# M228.net
KiCad netlist of a schematic drawn in EAGLE
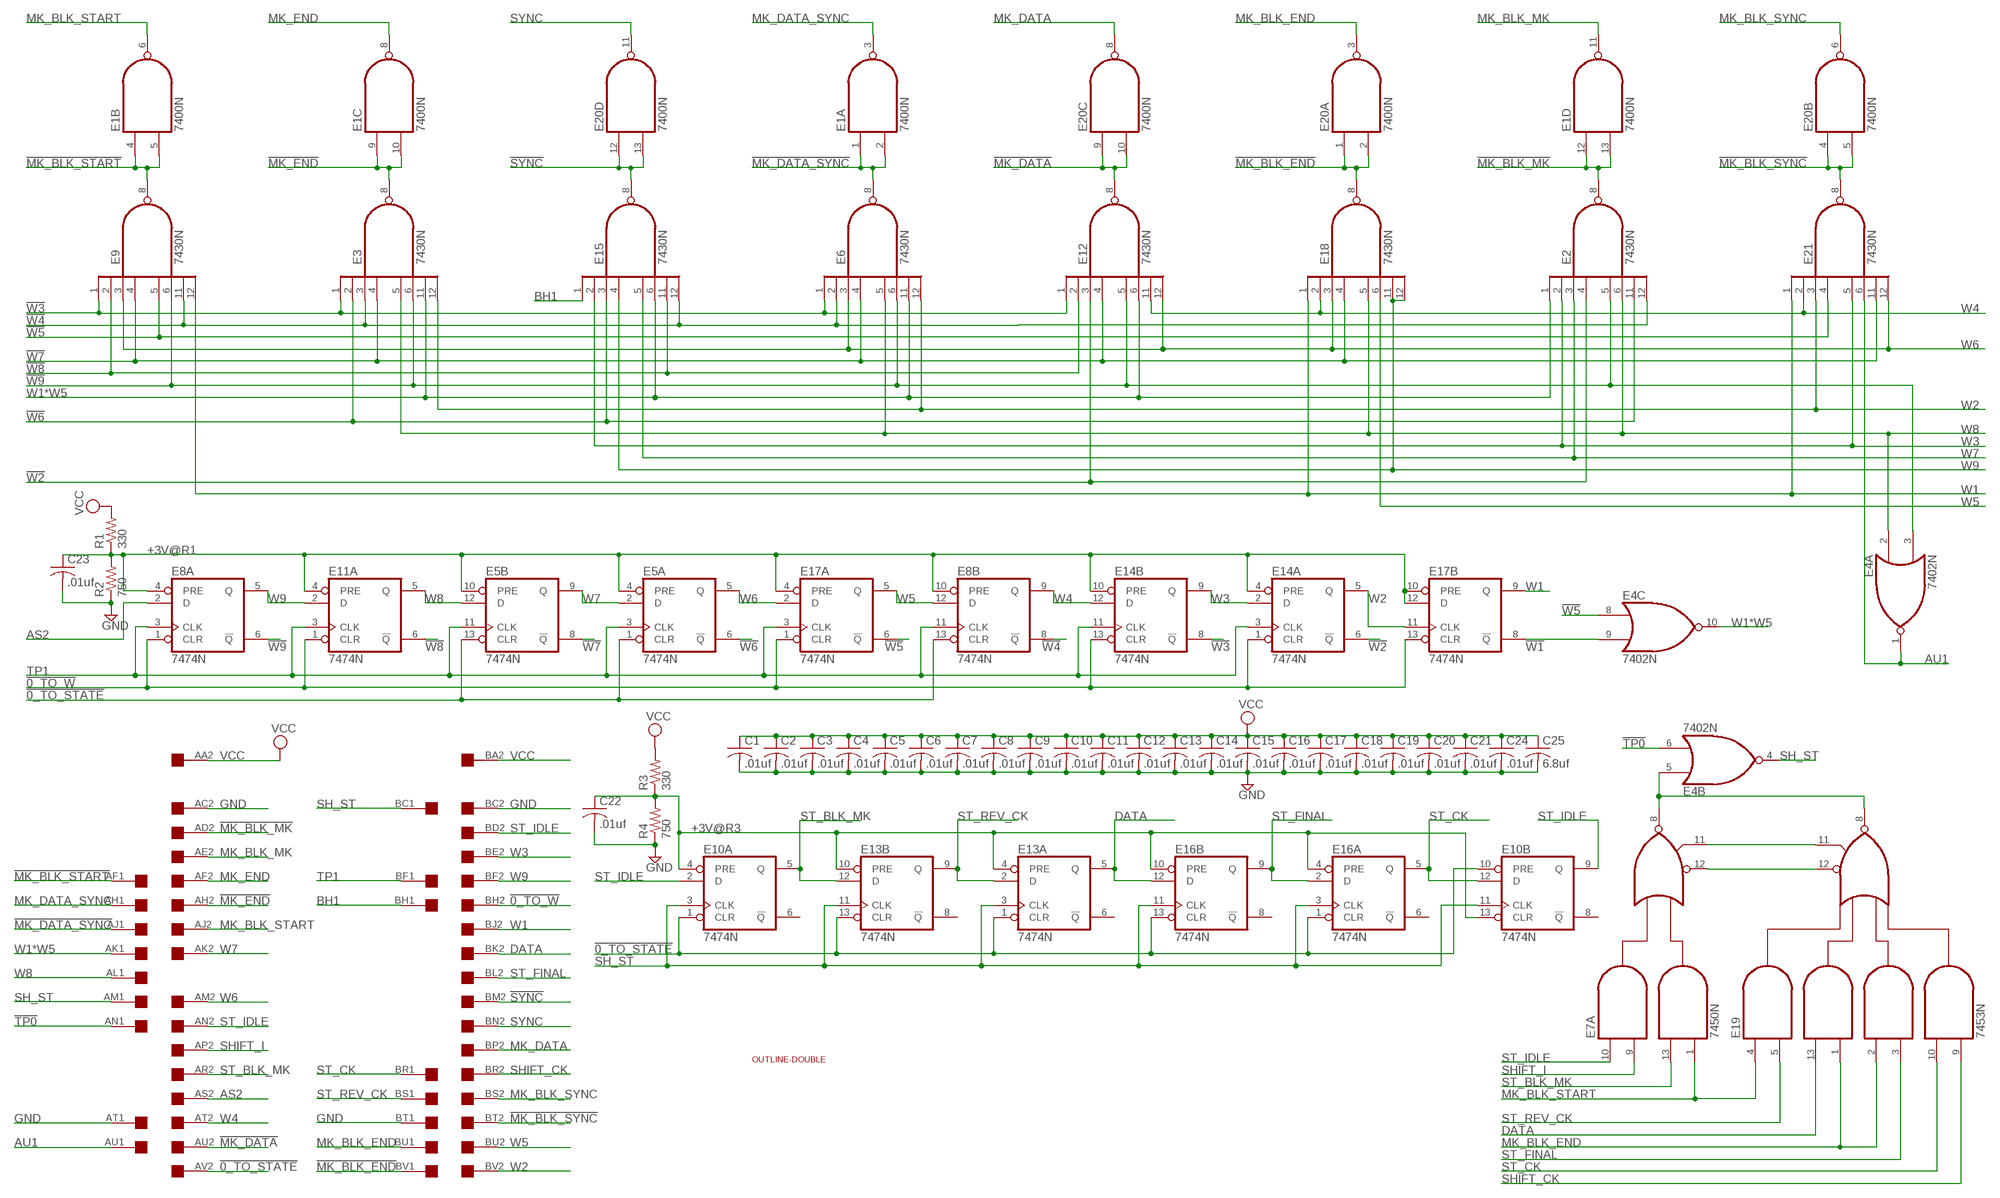
[diagram p0: schematic, sheet 1]

(export (version "E")
  (design (tool "Eeschema 10.0.6"))
  (components
    (comp (ref "C1")
      (value ".01uf")
      (footprint "eagle-import:C050-025X075")
      (libsource (lib "eagle-import") (part "C-US050-025X075"))
    )
    (comp (ref "C2")
      (value ".01uf")
      (footprint "eagle-import:C050-025X075")
      (libsource (lib "eagle-import") (part "C-US050-025X075"))
    )
    (comp (ref "C3")
      (value ".01uf")
      (footprint "eagle-import:C050-025X075")
      (libsource (lib "eagle-import") (part "C-US050-025X075"))
    )
    (comp (ref "C4")
      (value ".01uf")
      (footprint "eagle-import:C050-025X075")
      (libsource (lib "eagle-import") (part "C-US050-025X075"))
    )
    (comp (ref "C5")
      (value ".01uf")
      (footprint "eagle-import:C050-025X075")
      (libsource (lib "eagle-import") (part "C-US050-025X075"))
    )
    (comp (ref "C6")
      (value ".01uf")
      (footprint "eagle-import:C050-025X075")
      (libsource (lib "eagle-import") (part "C-US050-025X075"))
    )
    (comp (ref "C7")
      (value ".01uf")
      (footprint "eagle-import:C050-025X075")
      (libsource (lib "eagle-import") (part "C-US050-025X075"))
    )
    (comp (ref "C8")
      (value ".01uf")
      (footprint "eagle-import:C050-025X075")
      (libsource (lib "eagle-import") (part "C-US050-025X075"))
    )
    (comp (ref "C9")
      (value ".01uf")
      (footprint "eagle-import:C050-025X075")
      (libsource (lib "eagle-import") (part "C-US050-025X075"))
    )
    (comp (ref "C10")
      (value ".01uf")
      (footprint "eagle-import:C050-025X075")
      (libsource (lib "eagle-import") (part "C-US050-025X075"))
    )
    (comp (ref "C11")
      (value ".01uf")
      (footprint "eagle-import:C050-025X075")
      (libsource (lib "eagle-import") (part "C-US050-025X075"))
    )
    (comp (ref "C12")
      (value ".01uf")
      (footprint "eagle-import:C050-025X075")
      (libsource (lib "eagle-import") (part "C-US050-025X075"))
    )
    (comp (ref "C13")
      (value ".01uf")
      (footprint "eagle-import:C050-025X075")
      (libsource (lib "eagle-import") (part "C-US050-025X075"))
    )
    (comp (ref "C14")
      (value ".01uf")
      (footprint "eagle-import:C050-025X075")
      (libsource (lib "eagle-import") (part "C-US050-025X075"))
    )
    (comp (ref "C15")
      (value ".01uf")
      (footprint "eagle-import:C050-025X075")
      (libsource (lib "eagle-import") (part "C-US050-025X075"))
    )
    (comp (ref "C16")
      (value ".01uf")
      (footprint "eagle-import:C050-025X075")
      (libsource (lib "eagle-import") (part "C-US050-025X075"))
    )
    (comp (ref "C17")
      (value ".01uf")
      (footprint "eagle-import:C050-025X075")
      (libsource (lib "eagle-import") (part "C-US050-025X075"))
    )
    (comp (ref "C18")
      (value ".01uf")
      (footprint "eagle-import:C050-025X075")
      (libsource (lib "eagle-import") (part "C-US050-025X075"))
    )
    (comp (ref "C19")
      (value ".01uf")
      (footprint "eagle-import:C050-025X075")
      (libsource (lib "eagle-import") (part "C-US050-025X075"))
    )
    (comp (ref "C20")
      (value ".01uf")
      (footprint "eagle-import:C050-025X075")
      (libsource (lib "eagle-import") (part "C-US050-025X075"))
    )
    (comp (ref "C21")
      (value ".01uf")
      (footprint "eagle-import:C050-025X075")
      (libsource (lib "eagle-import") (part "C-US050-025X075"))
    )
    (comp (ref "C22")
      (value ".01uf")
      (footprint "eagle-import:C050-025X075")
      (libsource (lib "eagle-import") (part "C-US050-025X075"))
    )
    (comp (ref "C23")
      (value ".01uf")
      (footprint "eagle-import:C050-025X075")
      (libsource (lib "eagle-import") (part "C-US050-025X075"))
    )
    (comp (ref "C24")
      (value ".01uf")
      (footprint "eagle-import:C050-025X075")
      (libsource (lib "eagle-import") (part "C-US050-025X075"))
    )
    (comp (ref "C25")
      (value "6.8uf")
      (footprint "eagle-import:C150-054X183")
      (libsource (lib "eagle-import") (part "C-US150-054X183"))
    )
    (comp (ref "E1")
      (value "7400N")
      (footprint "eagle-import:DIL14")
      (libsource (lib "eagle-import") (part "7400N"))
    )
    (comp (ref "E2")
      (value "7430N")
      (footprint "eagle-import:DIL14")
      (libsource (lib "eagle-import") (part "7430N"))
    )
    (comp (ref "E3")
      (value "7430N")
      (footprint "eagle-import:DIL14")
      (libsource (lib "eagle-import") (part "7430N"))
    )
    (comp (ref "E4")
      (value "7402N")
      (footprint "eagle-import:DIL14")
      (libsource (lib "eagle-import") (part "7402N"))
    )
    (comp (ref "E5")
      (value "7474N")
      (footprint "eagle-import:DIL14")
      (libsource (lib "eagle-import") (part "7474NS"))
    )
    (comp (ref "E6")
      (value "7430N")
      (footprint "eagle-import:DIL14")
      (libsource (lib "eagle-import") (part "7430N"))
    )
    (comp (ref "E7")
      (value "7450N")
      (footprint "eagle-import:DIL14")
      (libsource (lib "eagle-import") (part "7450N"))
    )
    (comp (ref "E8")
      (value "7474N")
      (footprint "eagle-import:DIL14")
      (libsource (lib "eagle-import") (part "7474NS"))
    )
    (comp (ref "E9")
      (value "7430N")
      (footprint "eagle-import:DIL14")
      (libsource (lib "eagle-import") (part "7430N"))
    )
    (comp (ref "E10")
      (value "7474N")
      (footprint "eagle-import:DIL14")
      (libsource (lib "eagle-import") (part "7474NS"))
    )
    (comp (ref "E11")
      (value "7474N")
      (footprint "eagle-import:DIL14")
      (libsource (lib "eagle-import") (part "7474NS"))
    )
    (comp (ref "E12")
      (value "7430N")
      (footprint "eagle-import:DIL14")
      (libsource (lib "eagle-import") (part "7430N"))
    )
    (comp (ref "E13")
      (value "7474N")
      (footprint "eagle-import:DIL14")
      (libsource (lib "eagle-import") (part "7474NS"))
    )
    (comp (ref "E14")
      (value "7474N")
      (footprint "eagle-import:DIL14")
      (libsource (lib "eagle-import") (part "7474NS"))
    )
    (comp (ref "E15")
      (value "7430N")
      (footprint "eagle-import:DIL14")
      (libsource (lib "eagle-import") (part "7430N"))
    )
    (comp (ref "E16")
      (value "7474N")
      (footprint "eagle-import:DIL14")
      (libsource (lib "eagle-import") (part "7474NS"))
    )
    (comp (ref "E17")
      (value "7474N")
      (footprint "eagle-import:DIL14")
      (libsource (lib "eagle-import") (part "7474NS"))
    )
    (comp (ref "E18")
      (value "7430N")
      (footprint "eagle-import:DIL14")
      (libsource (lib "eagle-import") (part "7430N"))
    )
    (comp (ref "E19")
      (value "7453N")
      (footprint "eagle-import:DIL14")
      (libsource (lib "eagle-import") (part "7453N"))
    )
    (comp (ref "E20")
      (value "7400N")
      (footprint "eagle-import:DIL14")
      (libsource (lib "eagle-import") (part "7400N"))
    )
    (comp (ref "E21")
      (value "7430N")
      (footprint "eagle-import:DIL14")
      (libsource (lib "eagle-import") (part "7430N"))
    )
    (comp (ref "R1")
      (value "330")
      (footprint "eagle-import:0207_10")
      (libsource (lib "eagle-import") (part "R-US_0207/10"))
    )
    (comp (ref "R2")
      (value "750")
      (footprint "eagle-import:0207_10")
      (libsource (lib "eagle-import") (part "R-US_0207/10"))
    )
    (comp (ref "R3")
      (value "330")
      (footprint "eagle-import:0207_10")
      (libsource (lib "eagle-import") (part "R-US_0207/10"))
    )
    (comp (ref "R4")
      (value "750")
      (footprint "eagle-import:0207_10")
      (libsource (lib "eagle-import") (part "R-US_0207/10"))
    )
    (comp (ref "U$1")
      (value "OUTLINE-DOUBLE")
      (footprint "eagle-import:DOUBLE")
      (libsource (lib "eagle-import") (part "OUTLINE-DOUBLE"))
    )
    (comp (ref "U$5")
      (value "DOUBLE")
      (footprint "eagle-import:EDGE-CON4")
      (libsource (lib "eagle-import") (part "DOUBLE"))
    )
  )
  (nets
    (net (code "1") (name "/+3V@R1") (class "Default")
      (node (ref "C23") (pin "1") (pinfunction "1_1") (pintype "passive"))
      (node (ref "E11") (pin "4") (pinfunction "PRE_4") (pintype "input"))
      (node (ref "E14") (pin "10") (pinfunction "PRE_10") (pintype "input"))
      (node (ref "E14") (pin "4") (pinfunction "PRE_4") (pintype "input"))
      (node (ref "E17") (pin "10") (pinfunction "PRE_10") (pintype "input"))
      (node (ref "E17") (pin "12") (pinfunction "D_12") (pintype "input"))
      (node (ref "E17") (pin "4") (pinfunction "PRE_4") (pintype "input"))
      (node (ref "E5") (pin "10") (pinfunction "PRE_10") (pintype "input"))
      (node (ref "E5") (pin "4") (pinfunction "PRE_4") (pintype "input"))
      (node (ref "E8") (pin "10") (pinfunction "PRE_10") (pintype "input"))
      (node (ref "E8") (pin "4") (pinfunction "PRE_4") (pintype "input"))
      (node (ref "R1") (pin "1") (pinfunction "1_1") (pintype "passive"))
      (node (ref "R2") (pin "2") (pinfunction "2_2") (pintype "passive"))
    )
    (net (code "2") (name "/+3V@R3") (class "Default")
      (node (ref "C22") (pin "1") (pinfunction "1_1") (pintype "passive"))
      (node (ref "E10") (pin "13") (pinfunction "CLR_13") (pintype "input"))
      (node (ref "E10") (pin "4") (pinfunction "PRE_4") (pintype "input"))
      (node (ref "E13") (pin "10") (pinfunction "PRE_10") (pintype "input"))
      (node (ref "E13") (pin "4") (pinfunction "PRE_4") (pintype "input"))
      (node (ref "E16") (pin "10") (pinfunction "PRE_10") (pintype "input"))
      (node (ref "E16") (pin "4") (pinfunction "PRE_4") (pintype "input"))
      (node (ref "R3") (pin "1") (pinfunction "1_1") (pintype "passive"))
      (node (ref "R4") (pin "2") (pinfunction "2_2") (pintype "passive"))
    )
    (net (code "3") (name "/AS2") (class "Default")
      (node (ref "E8") (pin "2") (pinfunction "D_2") (pintype "input"))
      (node (ref "U$5") (pin "AS2") (pinfunction "1_AS2") (pintype "bidirectional"))
    )
    (net (code "4") (name "/AU1") (class "Default")
      (node (ref "E21") (pin "6") (pinfunction "I5_6") (pintype "input"))
      (node (ref "E4") (pin "1") (pinfunction "O_1") (pintype "output"))
      (node (ref "U$5") (pin "AU1") (pinfunction "1_AU1") (pintype "bidirectional"))
    )
    (net (code "5") (name "/BH1") (class "Default")
      (node (ref "E15") (pin "1") (pinfunction "I0_1") (pintype "input"))
      (node (ref "U$5") (pin "BH1") (pinfunction "1_BH1") (pintype "bidirectional"))
    )
    (net (code "6") (name "/DATA") (class "Default")
      (node (ref "E13") (pin "5") (pinfunction "Q_5") (pintype "output"))
      (node (ref "E16") (pin "12") (pinfunction "D_12") (pintype "input"))
      (node (ref "E19") (pin "13") (pinfunction "I3_13") (pintype "input"))
      (node (ref "U$5") (pin "BK2") (pinfunction "1_BK2") (pintype "bidirectional"))
    )
    (net (code "7") (name "/MK_BLK_END") (class "Default")
      (node (ref "E19") (pin "1") (pinfunction "I4_1") (pintype "input"))
      (node (ref "E19") (pin "2") (pinfunction "I5_2") (pintype "input"))
      (node (ref "E20") (pin "3") (pinfunction "O_3") (pintype "output"))
      (node (ref "U$5") (pin "BU1") (pinfunction "1_BU1") (pintype "bidirectional"))
    )
    (net (code "8") (name "/MK_BLK_MK") (class "Default")
      (node (ref "E1") (pin "11") (pinfunction "O_11") (pintype "output"))
      (node (ref "U$5") (pin "AE2") (pinfunction "1_AE2") (pintype "bidirectional"))
    )
    (net (code "9") (name "/MK_BLK_START") (class "Default")
      (node (ref "E1") (pin "6") (pinfunction "O_6") (pintype "output"))
      (node (ref "E19") (pin "4") (pinfunction "I1_4") (pintype "input"))
      (node (ref "E7") (pin "1") (pinfunction "I4_1") (pintype "input"))
      (node (ref "U$5") (pin "AJ2") (pinfunction "1_AJ2") (pintype "bidirectional"))
    )
    (net (code "10") (name "/MK_BLK_SYNC") (class "Default")
      (node (ref "E20") (pin "6") (pinfunction "O_6") (pintype "output"))
      (node (ref "U$5") (pin "BS2") (pinfunction "1_BS2") (pintype "bidirectional"))
    )
    (net (code "11") (name "/MK_DATA") (class "Default")
      (node (ref "E20") (pin "8") (pinfunction "O_8") (pintype "output"))
      (node (ref "U$5") (pin "BP2") (pinfunction "1_BP2") (pintype "bidirectional"))
    )
    (net (code "12") (name "/MK_DATA_SYNC") (class "Default")
      (node (ref "E1") (pin "3") (pinfunction "O_3") (pintype "output"))
      (node (ref "U$5") (pin "AH1") (pinfunction "1_AH1") (pintype "bidirectional"))
    )
    (net (code "13") (name "/MK_END") (class "Default")
      (node (ref "E1") (pin "8") (pinfunction "O_8") (pintype "output"))
      (node (ref "U$5") (pin "AF2") (pinfunction "1_AF2") (pintype "bidirectional"))
    )
    (net (code "14") (name "/SHIFT_CK") (class "Default")
      (node (ref "E19") (pin "9") (pinfunction "I8_9") (pintype "input"))
      (node (ref "U$5") (pin "BR2") (pinfunction "1_BR2") (pintype "bidirectional"))
    )
    (net (code "15") (name "/SHIFT_I") (class "Default")
      (node (ref "E7") (pin "9") (pinfunction "I2_9") (pintype "input"))
      (node (ref "U$5") (pin "AP2") (pinfunction "1_AP2") (pintype "bidirectional"))
    )
    (net (code "16") (name "/SH_ST") (class "Default")
      (node (ref "E10") (pin "11") (pinfunction "CLK_11") (pintype "input"))
      (node (ref "E10") (pin "3") (pinfunction "CLK_3") (pintype "input"))
      (node (ref "E13") (pin "11") (pinfunction "CLK_11") (pintype "input"))
      (node (ref "E13") (pin "3") (pinfunction "CLK_3") (pintype "input"))
      (node (ref "E16") (pin "11") (pinfunction "CLK_11") (pintype "input"))
      (node (ref "E16") (pin "3") (pinfunction "CLK_3") (pintype "input"))
      (node (ref "E4") (pin "4") (pinfunction "O_4") (pintype "output"))
      (node (ref "U$5") (pin "AM1") (pinfunction "1_AM1") (pintype "bidirectional"))
      (node (ref "U$5") (pin "BC1") (pinfunction "1_BC1") (pintype "bidirectional"))
    )
    (net (code "17") (name "/ST_BLK_MK") (class "Default")
      (node (ref "E10") (pin "5") (pinfunction "Q_5") (pintype "output"))
      (node (ref "E13") (pin "12") (pinfunction "D_12") (pintype "input"))
      (node (ref "E7") (pin "13") (pinfunction "I3_13") (pintype "input"))
      (node (ref "U$5") (pin "AR2") (pinfunction "1_AR2") (pintype "bidirectional"))
    )
    (net (code "18") (name "/ST_CK") (class "Default")
      (node (ref "E10") (pin "12") (pinfunction "D_12") (pintype "input"))
      (node (ref "E16") (pin "5") (pinfunction "Q_5") (pintype "output"))
      (node (ref "E19") (pin "10") (pinfunction "I7_10") (pintype "input"))
      (node (ref "U$5") (pin "BR1") (pinfunction "1_BR1") (pintype "bidirectional"))
    )
    (net (code "19") (name "/ST_FINAL") (class "Default")
      (node (ref "E16") (pin "2") (pinfunction "D_2") (pintype "input"))
      (node (ref "E16") (pin "9") (pinfunction "Q_9") (pintype "output"))
      (node (ref "E19") (pin "3") (pinfunction "I6_3") (pintype "input"))
      (node (ref "U$5") (pin "BL2") (pinfunction "1_BL2") (pintype "bidirectional"))
    )
    (net (code "20") (name "/ST_IDLE") (class "Default")
      (node (ref "E10") (pin "2") (pinfunction "D_2") (pintype "input"))
      (node (ref "E10") (pin "9") (pinfunction "Q_9") (pintype "output"))
      (node (ref "E7") (pin "10") (pinfunction "I1_10") (pintype "input"))
      (node (ref "U$5") (pin "AN2") (pinfunction "1_AN2") (pintype "bidirectional"))
      (node (ref "U$5") (pin "BD2") (pinfunction "1_BD2") (pintype "bidirectional"))
    )
    (net (code "21") (name "/ST_REV_CK") (class "Default")
      (node (ref "E13") (pin "2") (pinfunction "D_2") (pintype "input"))
      (node (ref "E13") (pin "9") (pinfunction "Q_9") (pintype "output"))
      (node (ref "E19") (pin "5") (pinfunction "I2_5") (pintype "input"))
      (node (ref "U$5") (pin "BS1") (pinfunction "1_BS1") (pintype "bidirectional"))
    )
    (net (code "22") (name "/SYNC") (class "Default")
      (node (ref "E20") (pin "11") (pinfunction "O_11") (pintype "output"))
      (node (ref "U$5") (pin "BN2") (pinfunction "1_BN2") (pintype "bidirectional"))
    )
    (net (code "23") (name "/TP1") (class "Default")
      (node (ref "E11") (pin "3") (pinfunction "CLK_3") (pintype "input"))
      (node (ref "E14") (pin "11") (pinfunction "CLK_11") (pintype "input"))
      (node (ref "E14") (pin "3") (pinfunction "CLK_3") (pintype "input"))
      (node (ref "E17") (pin "3") (pinfunction "CLK_3") (pintype "input"))
      (node (ref "E5") (pin "11") (pinfunction "CLK_11") (pintype "input"))
      (node (ref "E5") (pin "3") (pinfunction "CLK_3") (pintype "input"))
      (node (ref "E8") (pin "11") (pinfunction "CLK_11") (pintype "input"))
      (node (ref "E8") (pin "3") (pinfunction "CLK_3") (pintype "input"))
      (node (ref "U$5") (pin "BF1") (pinfunction "1_BF1") (pintype "bidirectional"))
    )
    (net (code "24") (name "/W1") (class "Default")
      (node (ref "E17") (pin "9") (pinfunction "Q_9") (pintype "output"))
      (node (ref "E18") (pin "1") (pinfunction "I0_1") (pintype "input"))
      (node (ref "E21") (pin "1") (pinfunction "I0_1") (pintype "input"))
      (node (ref "E9") (pin "12") (pinfunction "I7_12") (pintype "input"))
      (node (ref "U$5") (pin "BJ2") (pinfunction "1_BJ2") (pintype "bidirectional"))
    )
    (net (code "25") (name "/W1*W5") (class "Default")
      (node (ref "E12") (pin "6") (pinfunction "I5_6") (pintype "input"))
      (node (ref "E15") (pin "6") (pinfunction "I5_6") (pintype "input"))
      (node (ref "E2") (pin "1") (pinfunction "I0_1") (pintype "input"))
      (node (ref "E3") (pin "11") (pinfunction "I6_11") (pintype "input"))
      (node (ref "E4") (pin "10") (pinfunction "O_10") (pintype "output"))
      (node (ref "E6") (pin "11") (pinfunction "I6_11") (pintype "input"))
      (node (ref "U$5") (pin "AK1") (pinfunction "1_AK1") (pintype "bidirectional"))
    )
    (net (code "26") (name "/W2") (class "Default")
      (node (ref "E14") (pin "5") (pinfunction "Q_5") (pintype "output"))
      (node (ref "E17") (pin "11") (pinfunction "CLK_11") (pintype "input"))
      (node (ref "E21") (pin "3") (pinfunction "I2_3") (pintype "input"))
      (node (ref "E3") (pin "12") (pinfunction "I7_12") (pintype "input"))
      (node (ref "E6") (pin "12") (pinfunction "I7_12") (pintype "input"))
      (node (ref "U$5") (pin "BV2") (pinfunction "1_BV2") (pintype "bidirectional"))
    )
    (net (code "27") (name "/W3") (class "Default")
      (node (ref "E14") (pin "2") (pinfunction "D_2") (pintype "input"))
      (node (ref "E14") (pin "9") (pinfunction "Q_9") (pintype "output"))
      (node (ref "E15") (pin "2") (pinfunction "I1_2") (pintype "input"))
      (node (ref "E2") (pin "2") (pinfunction "I1_2") (pintype "input"))
      (node (ref "E21") (pin "5") (pinfunction "I4_5") (pintype "input"))
      (node (ref "U$5") (pin "BE2") (pinfunction "1_BE2") (pintype "bidirectional"))
    )
    (net (code "28") (name "/W4") (class "Default")
      (node (ref "E12") (pin "11") (pinfunction "I6_11") (pintype "input"))
      (node (ref "E14") (pin "12") (pinfunction "D_12") (pintype "input"))
      (node (ref "E18") (pin "2") (pinfunction "I1_2") (pintype "input"))
      (node (ref "E21") (pin "2") (pinfunction "I1_2") (pintype "input"))
      (node (ref "E8") (pin "9") (pinfunction "Q_9") (pintype "output"))
      (node (ref "U$5") (pin "AT2") (pinfunction "1_AT2") (pintype "bidirectional"))
    )
    (net (code "29") (name "/W5") (class "Default")
      (node (ref "E17") (pin "5") (pinfunction "Q_5") (pintype "output"))
      (node (ref "E18") (pin "6") (pinfunction "I5_6") (pintype "input"))
      (node (ref "E8") (pin "12") (pinfunction "D_12") (pintype "input"))
      (node (ref "U$5") (pin "BU2") (pinfunction "1_BU2") (pintype "bidirectional"))
    )
    (net (code "30") (name "/W6") (class "Default")
      (node (ref "E12") (pin "12") (pinfunction "I7_12") (pintype "input"))
      (node (ref "E17") (pin "2") (pinfunction "D_2") (pintype "input"))
      (node (ref "E18") (pin "3") (pinfunction "I2_3") (pintype "input"))
      (node (ref "E21") (pin "12") (pinfunction "I7_12") (pintype "input"))
      (node (ref "E5") (pin "5") (pinfunction "Q_5") (pintype "output"))
      (node (ref "E6") (pin "3") (pinfunction "I2_3") (pintype "input"))
      (node (ref "E9") (pin "3") (pinfunction "I2_3") (pintype "input"))
      (node (ref "U$5") (pin "AM2") (pinfunction "1_AM2") (pintype "bidirectional"))
    )
    (net (code "31") (name "/W7") (class "Default")
      (node (ref "E15") (pin "5") (pinfunction "I4_5") (pintype "input"))
      (node (ref "E2") (pin "3") (pinfunction "I2_3") (pintype "input"))
      (node (ref "E5") (pin "2") (pinfunction "D_2") (pintype "input"))
      (node (ref "E5") (pin "9") (pinfunction "Q_9") (pintype "output"))
      (node (ref "U$5") (pin "AK2") (pinfunction "1_AK2") (pintype "bidirectional"))
    )
    (net (code "32") (name "/W8") (class "Default")
      (node (ref "E11") (pin "5") (pinfunction "Q_5") (pintype "output"))
      (node (ref "E18") (pin "5") (pinfunction "I4_5") (pintype "input"))
      (node (ref "E2") (pin "6") (pinfunction "I5_6") (pintype "input"))
      (node (ref "E3") (pin "5") (pinfunction "I4_5") (pintype "input"))
      (node (ref "E4") (pin "2") (pinfunction "I0_2") (pintype "input"))
      (node (ref "E5") (pin "12") (pinfunction "D_12") (pintype "input"))
      (node (ref "E6") (pin "5") (pinfunction "I4_5") (pintype "input"))
      (node (ref "U$5") (pin "AL1") (pinfunction "1_AL1") (pintype "bidirectional"))
    )
    (net (code "33") (name "/W9") (class "Default")
      (node (ref "E11") (pin "2") (pinfunction "D_2") (pintype "input"))
      (node (ref "E15") (pin "4") (pinfunction "I3_4") (pintype "input"))
      (node (ref "E18") (pin "11") (pinfunction "I6_11") (pintype "input"))
      (node (ref "E18") (pin "12") (pinfunction "I7_12") (pintype "input"))
      (node (ref "E8") (pin "5") (pinfunction "Q_5") (pintype "output"))
      (node (ref "U$5") (pin "BF2") (pinfunction "1_BF2") (pintype "bidirectional"))
    )
    (net (code "34") (name "/~{0_TO_STATE}") (class "Default")
      (node (ref "E10") (pin "1") (pinfunction "CLR_1") (pintype "input"))
      (node (ref "E10") (pin "10") (pinfunction "PRE_10") (pintype "input"))
      (node (ref "E13") (pin "1") (pinfunction "CLR_1") (pintype "input"))
      (node (ref "E13") (pin "13") (pinfunction "CLR_13") (pintype "input"))
      (node (ref "E16") (pin "1") (pinfunction "CLR_1") (pintype "input"))
      (node (ref "E16") (pin "13") (pinfunction "CLR_13") (pintype "input"))
      (node (ref "E5") (pin "1") (pinfunction "CLR_1") (pintype "input"))
      (node (ref "E5") (pin "13") (pinfunction "CLR_13") (pintype "input"))
      (node (ref "E8") (pin "13") (pinfunction "CLR_13") (pintype "input"))
      (node (ref "U$5") (pin "AV2") (pinfunction "1_AV2") (pintype "bidirectional"))
    )
    (net (code "35") (name "/~{0_TO_W}") (class "Default")
      (node (ref "E11") (pin "1") (pinfunction "CLR_1") (pintype "input"))
      (node (ref "E14") (pin "1") (pinfunction "CLR_1") (pintype "input"))
      (node (ref "E14") (pin "13") (pinfunction "CLR_13") (pintype "input"))
      (node (ref "E17") (pin "1") (pinfunction "CLR_1") (pintype "input"))
      (node (ref "E17") (pin "13") (pinfunction "CLR_13") (pintype "input"))
      (node (ref "E8") (pin "1") (pinfunction "CLR_1") (pintype "input"))
      (node (ref "U$5") (pin "BH2") (pinfunction "1_BH2") (pintype "bidirectional"))
    )
    (net (code "36") (name "/~{MK_BLK_END}") (class "Default")
      (node (ref "E18") (pin "8") (pinfunction "O_8") (pintype "output"))
      (node (ref "E20") (pin "1") (pinfunction "I0_1") (pintype "input"))
      (node (ref "E20") (pin "2") (pinfunction "I1_2") (pintype "input"))
      (node (ref "U$5") (pin "BV1") (pinfunction "1_BV1") (pintype "bidirectional"))
    )
    (net (code "37") (name "/~{MK_BLK_MK}") (class "Default")
      (node (ref "E1") (pin "12") (pinfunction "I0_12") (pintype "input"))
      (node (ref "E1") (pin "13") (pinfunction "I1_13") (pintype "input"))
      (node (ref "E2") (pin "8") (pinfunction "O_8") (pintype "output"))
      (node (ref "U$5") (pin "AD2") (pinfunction "1_AD2") (pintype "bidirectional"))
    )
    (net (code "38") (name "/~{MK_BLK_START}") (class "Default")
      (node (ref "E1") (pin "4") (pinfunction "I0_4") (pintype "input"))
      (node (ref "E1") (pin "5") (pinfunction "I1_5") (pintype "input"))
      (node (ref "E9") (pin "8") (pinfunction "O_8") (pintype "output"))
      (node (ref "U$5") (pin "AF1") (pinfunction "1_AF1") (pintype "bidirectional"))
    )
    (net (code "39") (name "/~{MK_BLK_SYNC}") (class "Default")
      (node (ref "E20") (pin "4") (pinfunction "I0_4") (pintype "input"))
      (node (ref "E20") (pin "5") (pinfunction "I1_5") (pintype "input"))
      (node (ref "E21") (pin "8") (pinfunction "O_8") (pintype "output"))
      (node (ref "U$5") (pin "BT2") (pinfunction "1_BT2") (pintype "bidirectional"))
    )
    (net (code "40") (name "/~{MK_DATA_SYNC}") (class "Default")
      (node (ref "E1") (pin "1") (pinfunction "I0_1") (pintype "input"))
      (node (ref "E1") (pin "2") (pinfunction "I1_2") (pintype "input"))
      (node (ref "E6") (pin "8") (pinfunction "O_8") (pintype "output"))
      (node (ref "U$5") (pin "AJ1") (pinfunction "1_AJ1") (pintype "bidirectional"))
    )
    (net (code "41") (name "/~{MK_DATA}") (class "Default")
      (node (ref "E12") (pin "8") (pinfunction "O_8") (pintype "output"))
      (node (ref "E20") (pin "10") (pinfunction "I1_10") (pintype "input"))
      (node (ref "E20") (pin "9") (pinfunction "I0_9") (pintype "input"))
      (node (ref "U$5") (pin "AU2") (pinfunction "1_AU2") (pintype "bidirectional"))
    )
    (net (code "42") (name "/~{MK_END}") (class "Default")
      (node (ref "E1") (pin "10") (pinfunction "I1_10") (pintype "input"))
      (node (ref "E1") (pin "9") (pinfunction "I0_9") (pintype "input"))
      (node (ref "E3") (pin "8") (pinfunction "O_8") (pintype "output"))
      (node (ref "U$5") (pin "AH2") (pinfunction "1_AH2") (pintype "bidirectional"))
    )
    (net (code "43") (name "/~{SYNC}") (class "Default")
      (node (ref "E15") (pin "8") (pinfunction "O_8") (pintype "output"))
      (node (ref "E20") (pin "12") (pinfunction "I0_12") (pintype "input"))
      (node (ref "E20") (pin "13") (pinfunction "I1_13") (pintype "input"))
      (node (ref "U$5") (pin "BM2") (pinfunction "1_BM2") (pintype "bidirectional"))
    )
    (net (code "44") (name "/~{TP0}") (class "Default")
      (node (ref "E4") (pin "6") (pinfunction "I1_6") (pintype "input"))
      (node (ref "U$5") (pin "AN1") (pinfunction "1_AN1") (pintype "bidirectional"))
    )
    (net (code "45") (name "/~{W1}") (class "Default")
      (node (ref "E17") (pin "8") (pinfunction "~{Q}_8") (pintype "output"))
      (node (ref "E4") (pin "9") (pinfunction "I1_9") (pintype "input"))
    )
    (net (code "46") (name "/~{W2}") (class "Default")
      (node (ref "E12") (pin "3") (pinfunction "I2_3") (pintype "input"))
      (node (ref "E14") (pin "6") (pinfunction "~{Q}_6") (pintype "output"))
      (node (ref "E2") (pin "4") (pinfunction "I3_4") (pintype "input"))
    )
    (net (code "47") (name "/~{W3}") (class "Default")
      (node (ref "E12") (pin "1") (pinfunction "I0_1") (pintype "input"))
      (node (ref "E14") (pin "8") (pinfunction "~{Q}_8") (pintype "output"))
      (node (ref "E3") (pin "1") (pinfunction "I0_1") (pintype "input"))
      (node (ref "E6") (pin "1") (pinfunction "I0_1") (pintype "input"))
      (node (ref "E9") (pin "1") (pinfunction "I0_1") (pintype "input"))
    )
    (net (code "48") (name "/~{W4}") (class "Default")
      (node (ref "E15") (pin "12") (pinfunction "I7_12") (pintype "input"))
      (node (ref "E2") (pin "12") (pinfunction "I7_12") (pintype "input"))
      (node (ref "E3") (pin "3") (pinfunction "I2_3") (pintype "input"))
      (node (ref "E6") (pin "2") (pinfunction "I1_2") (pintype "input"))
      (node (ref "E8") (pin "8") (pinfunction "~{Q}_8") (pintype "output"))
      (node (ref "E9") (pin "11") (pinfunction "I6_11") (pintype "input"))
    )
    (net (code "49") (name "/~{W5}") (class "Default")
      (node (ref "E17") (pin "6") (pinfunction "~{Q}_6") (pintype "output"))
      (node (ref "E21") (pin "4") (pinfunction "I3_4") (pintype "input"))
      (node (ref "E4") (pin "8") (pinfunction "I0_8") (pintype "input"))
      (node (ref "E9") (pin "5") (pinfunction "I4_5") (pintype "input"))
    )
    (net (code "50") (name "/~{W6}") (class "Default")
      (node (ref "E15") (pin "3") (pinfunction "I2_3") (pintype "input"))
      (node (ref "E2") (pin "11") (pinfunction "I6_11") (pintype "input"))
      (node (ref "E3") (pin "2") (pinfunction "I1_2") (pintype "input"))
      (node (ref "E5") (pin "6") (pinfunction "~{Q}_6") (pintype "output"))
    )
    (net (code "51") (name "/~{W7}") (class "Default")
      (node (ref "E12") (pin "4") (pinfunction "I3_4") (pintype "input"))
      (node (ref "E18") (pin "4") (pinfunction "I3_4") (pintype "input"))
      (node (ref "E21") (pin "11") (pinfunction "I6_11") (pintype "input"))
      (node (ref "E3") (pin "4") (pinfunction "I3_4") (pintype "input"))
      (node (ref "E5") (pin "8") (pinfunction "~{Q}_8") (pintype "output"))
      (node (ref "E6") (pin "4") (pinfunction "I3_4") (pintype "input"))
      (node (ref "E9") (pin "4") (pinfunction "I3_4") (pintype "input"))
    )
    (net (code "52") (name "/~{W8}") (class "Default")
      (node (ref "E11") (pin "6") (pinfunction "~{Q}_6") (pintype "output"))
      (node (ref "E12") (pin "2") (pinfunction "I1_2") (pintype "input"))
      (node (ref "E15") (pin "11") (pinfunction "I6_11") (pintype "input"))
      (node (ref "E9") (pin "2") (pinfunction "I1_2") (pintype "input"))
    )
    (net (code "53") (name "/~{W9}") (class "Default")
      (node (ref "E12") (pin "5") (pinfunction "I4_5") (pintype "input"))
      (node (ref "E2") (pin "5") (pinfunction "I4_5") (pintype "input"))
      (node (ref "E3") (pin "6") (pinfunction "I5_6") (pintype "input"))
      (node (ref "E4") (pin "3") (pinfunction "I1_3") (pintype "input"))
      (node (ref "E6") (pin "6") (pinfunction "I5_6") (pintype "input"))
      (node (ref "E8") (pin "6") (pinfunction "~{Q}_6") (pintype "output"))
      (node (ref "E9") (pin "6") (pinfunction "I5_6") (pintype "input"))
    )
    (net (code "54") (name "GND") (class "Default")
      (node (ref "C1") (pin "2") (pinfunction "2_2") (pintype "passive"))
      (node (ref "C10") (pin "2") (pinfunction "2_2") (pintype "passive"))
      (node (ref "C11") (pin "2") (pinfunction "2_2") (pintype "passive"))
      (node (ref "C12") (pin "2") (pinfunction "2_2") (pintype "passive"))
      (node (ref "C13") (pin "2") (pinfunction "2_2") (pintype "passive"))
      (node (ref "C14") (pin "2") (pinfunction "2_2") (pintype "passive"))
      (node (ref "C15") (pin "2") (pinfunction "2_2") (pintype "passive"))
      (node (ref "C16") (pin "2") (pinfunction "2_2") (pintype "passive"))
      (node (ref "C17") (pin "2") (pinfunction "2_2") (pintype "passive"))
      (node (ref "C18") (pin "2") (pinfunction "2_2") (pintype "passive"))
      (node (ref "C19") (pin "2") (pinfunction "2_2") (pintype "passive"))
      (node (ref "C2") (pin "2") (pinfunction "2_2") (pintype "passive"))
      (node (ref "C20") (pin "2") (pinfunction "2_2") (pintype "passive"))
      (node (ref "C21") (pin "2") (pinfunction "2_2") (pintype "passive"))
      (node (ref "C22") (pin "2") (pinfunction "2_2") (pintype "passive"))
      (node (ref "C23") (pin "2") (pinfunction "2_2") (pintype "passive"))
      (node (ref "C24") (pin "2") (pinfunction "2_2") (pintype "passive"))
      (node (ref "C25") (pin "2") (pinfunction "2_2") (pintype "passive"))
      (node (ref "C3") (pin "2") (pinfunction "2_2") (pintype "passive"))
      (node (ref "C4") (pin "2") (pinfunction "2_2") (pintype "passive"))
      (node (ref "C5") (pin "2") (pinfunction "2_2") (pintype "passive"))
      (node (ref "C6") (pin "2") (pinfunction "2_2") (pintype "passive"))
      (node (ref "C7") (pin "2") (pinfunction "2_2") (pintype "passive"))
      (node (ref "C8") (pin "2") (pinfunction "2_2") (pintype "passive"))
      (node (ref "C9") (pin "2") (pinfunction "2_2") (pintype "passive"))
      (node (ref "R2") (pin "1") (pinfunction "1_1") (pintype "passive"))
      (node (ref "R4") (pin "1") (pinfunction "1_1") (pintype "passive"))
      (node (ref "U$5") (pin "AC2") (pinfunction "1_AC2") (pintype "bidirectional"))
      (node (ref "U$5") (pin "AT1") (pinfunction "1_AT1") (pintype "bidirectional"))
      (node (ref "U$5") (pin "BC2") (pinfunction "1_BC2") (pintype "bidirectional"))
      (node (ref "U$5") (pin "BT1") (pinfunction "1_BT1") (pintype "bidirectional"))
    )
    (net (code "55") (name "Net-(E19A-I9)") (class "Default")
      (node (ref "E19") (pin "12") (pinfunction "I9_12") (pintype "passive"))
      (node (ref "E7") (pin "12") (pinfunction "I5_12") (pintype "passive"))
    )
    (net (code "56") (name "Net-(E19A-I10)") (class "Default")
      (node (ref "E19") (pin "11") (pinfunction "I10_11") (pintype "passive"))
      (node (ref "E7") (pin "11") (pinfunction "I6_11") (pintype "passive"))
    )
    (net (code "57") (name "Net-(E19A-O)") (class "Default")
      (node (ref "E19") (pin "8") (pinfunction "O_8") (pintype "output"))
      (node (ref "E4") (pin "5") (pinfunction "I0_5") (pintype "input"))
      (node (ref "E7") (pin "8") (pinfunction "O_8") (pintype "output"))
    )
    (net (code "58") (name "VCC") (class "Default")
      (node (ref "C1") (pin "1") (pinfunction "1_1") (pintype "passive"))
      (node (ref "C10") (pin "1") (pinfunction "1_1") (pintype "passive"))
      (node (ref "C11") (pin "1") (pinfunction "1_1") (pintype "passive"))
      (node (ref "C12") (pin "1") (pinfunction "1_1") (pintype "passive"))
      (node (ref "C13") (pin "1") (pinfunction "1_1") (pintype "passive"))
      (node (ref "C14") (pin "1") (pinfunction "1_1") (pintype "passive"))
      (node (ref "C15") (pin "1") (pinfunction "1_1") (pintype "passive"))
      (node (ref "C16") (pin "1") (pinfunction "1_1") (pintype "passive"))
      (node (ref "C17") (pin "1") (pinfunction "1_1") (pintype "passive"))
      (node (ref "C18") (pin "1") (pinfunction "1_1") (pintype "passive"))
      (node (ref "C19") (pin "1") (pinfunction "1_1") (pintype "passive"))
      (node (ref "C2") (pin "1") (pinfunction "1_1") (pintype "passive"))
      (node (ref "C20") (pin "1") (pinfunction "1_1") (pintype "passive"))
      (node (ref "C21") (pin "1") (pinfunction "1_1") (pintype "passive"))
      (node (ref "C24") (pin "1") (pinfunction "1_1") (pintype "passive"))
      (node (ref "C25") (pin "1") (pinfunction "1_1") (pintype "passive"))
      (node (ref "C3") (pin "1") (pinfunction "1_1") (pintype "passive"))
      (node (ref "C4") (pin "1") (pinfunction "1_1") (pintype "passive"))
      (node (ref "C5") (pin "1") (pinfunction "1_1") (pintype "passive"))
      (node (ref "C6") (pin "1") (pinfunction "1_1") (pintype "passive"))
      (node (ref "C7") (pin "1") (pinfunction "1_1") (pintype "passive"))
      (node (ref "C8") (pin "1") (pinfunction "1_1") (pintype "passive"))
      (node (ref "C9") (pin "1") (pinfunction "1_1") (pintype "passive"))
      (node (ref "R1") (pin "2") (pinfunction "2_2") (pintype "passive"))
      (node (ref "R3") (pin "2") (pinfunction "2_2") (pintype "passive"))
      (node (ref "U$5") (pin "AA2") (pinfunction "1_AA2") (pintype "bidirectional"))
      (node (ref "U$5") (pin "BA2") (pinfunction "1_BA2") (pintype "bidirectional"))
    )
    (net (code "59") (name "unconnected-(E10A-~{Q}-Pad6)") (class "Default")
      (node (ref "E10") (pin "6") (pinfunction "~{Q}_6") (pintype "output"))
    )
    (net (code "60") (name "unconnected-(E10B-~{Q}-Pad8)") (class "Default")
      (node (ref "E10") (pin "8") (pinfunction "~{Q}_8") (pintype "output"))
    )
    (net (code "61") (name "unconnected-(E13A-~{Q}-Pad6)") (class "Default")
      (node (ref "E13") (pin "6") (pinfunction "~{Q}_6") (pintype "output"))
    )
    (net (code "62") (name "unconnected-(E13B-~{Q}-Pad8)") (class "Default")
      (node (ref "E13") (pin "8") (pinfunction "~{Q}_8") (pintype "output"))
    )
    (net (code "63") (name "unconnected-(E16A-~{Q}-Pad6)") (class "Default")
      (node (ref "E16") (pin "6") (pinfunction "~{Q}_6") (pintype "output"))
    )
    (net (code "64") (name "unconnected-(E16B-~{Q}-Pad8)") (class "Default")
      (node (ref "E16") (pin "8") (pinfunction "~{Q}_8") (pintype "output"))
    )
  )
)
